# AEMSUCA-R3.net
KiCad netlist of a schematic drawn in EAGLE
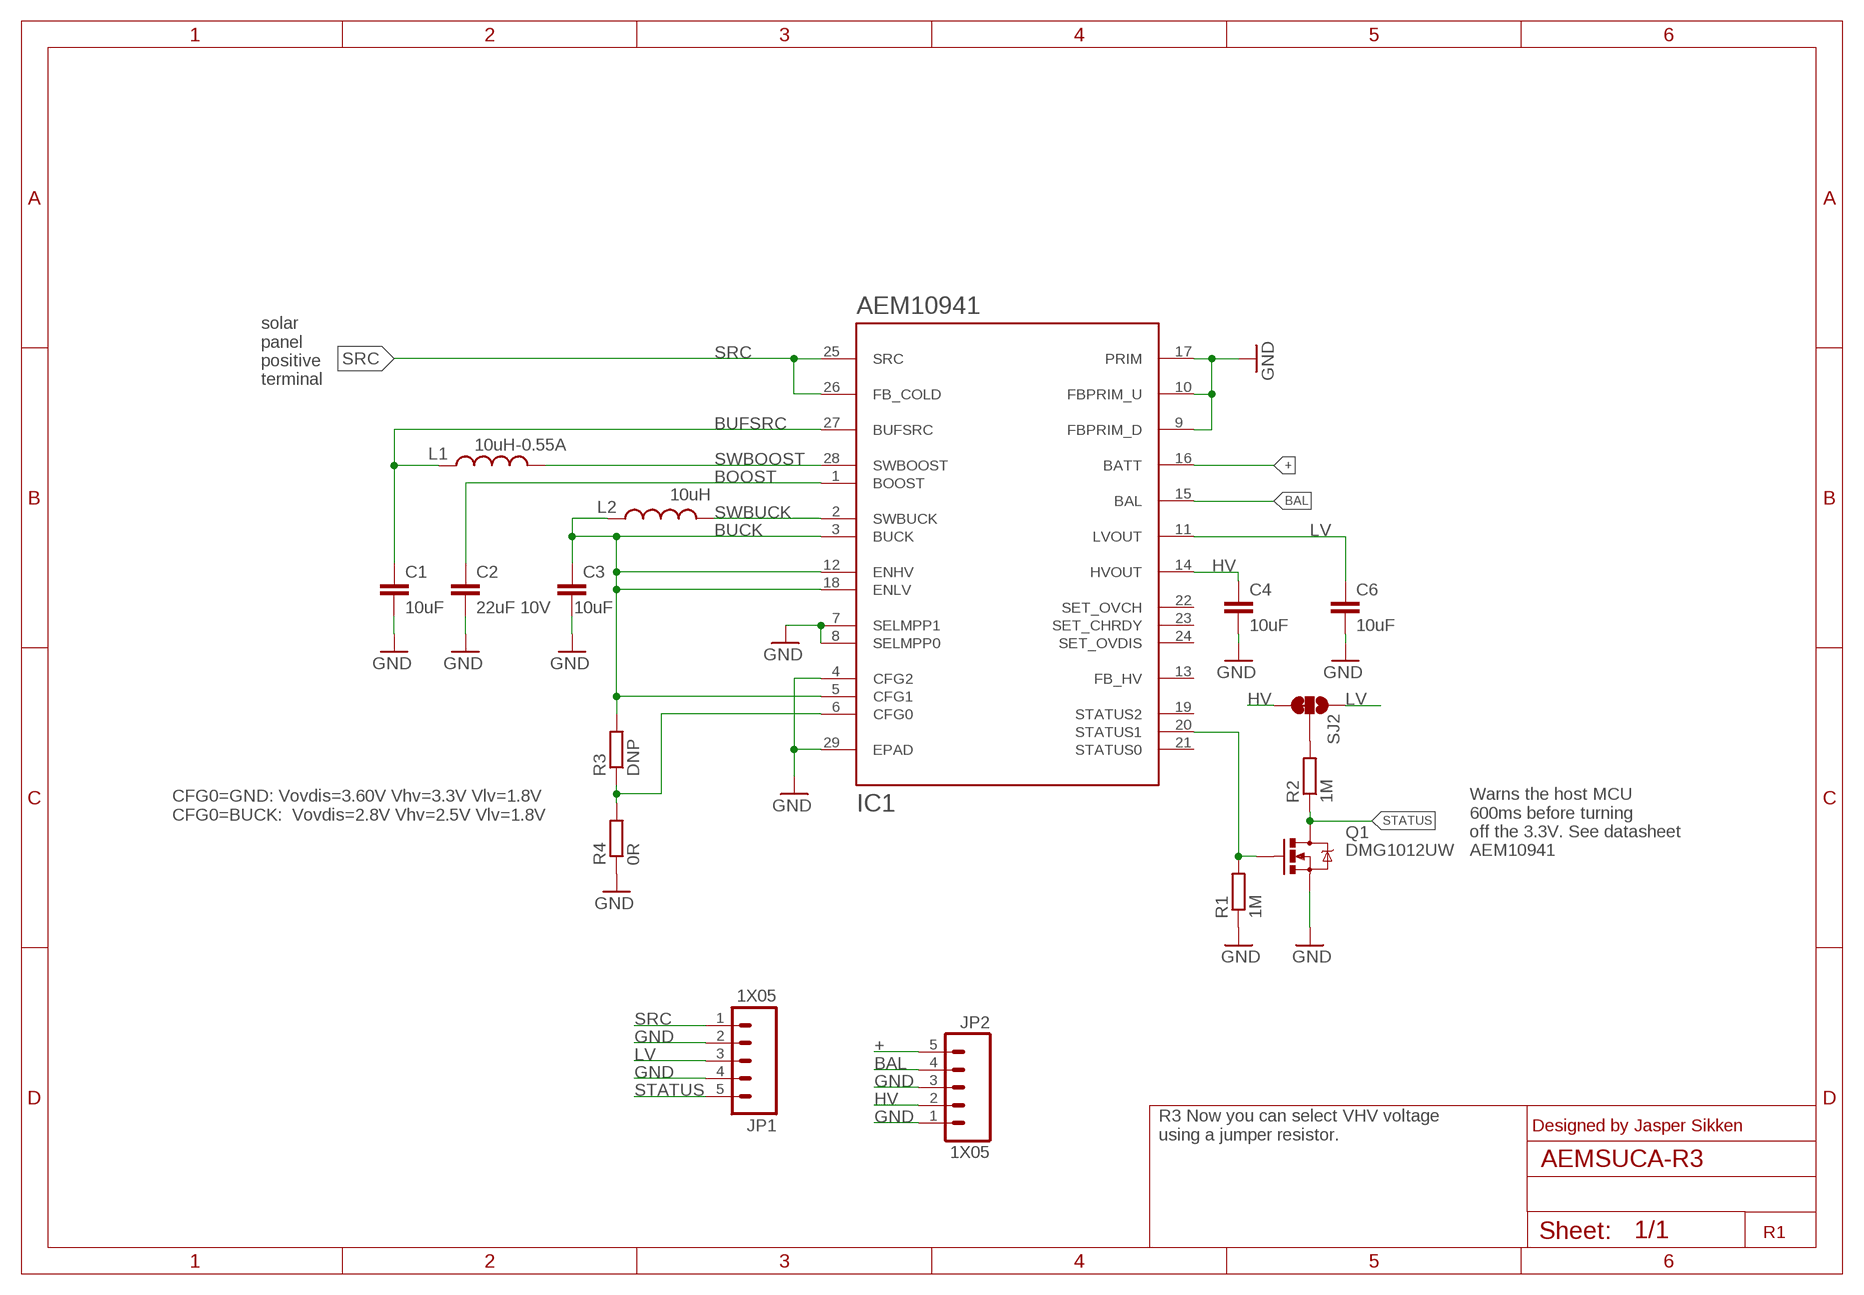
[diagram p0: schematic, sheet 1]

(export (version "E")
  (design (tool "Eeschema 10.0.6"))
  (components
    (comp (ref "C1")
      (value "10uF")
      (footprint "eagle-import:C0603")
      (fields (field (name "MF") "Taiyo Yuden") (field (name "MPN") "LMK107BBJ106MALT"))
      (libsource (lib "eagle-import") (part "C0603_10UF"))
    )
    (comp (ref "C2")
      (value "22uF 10V")
      (footprint "eagle-import:C0603")
      (fields (field (name "MF") "Murata") (field (name "MPN") "GRM188R61A226ME15D"))
      (libsource (lib "eagle-import") (part "C0603_22UF"))
    )
    (comp (ref "C3")
      (value "10uF")
      (footprint "eagle-import:C0603")
      (fields (field (name "MF") "Taiyo Yuden") (field (name "MPN") "LMK107BBJ106MALT"))
      (libsource (lib "eagle-import") (part "C0603_10UF"))
    )
    (comp (ref "C4")
      (value "10uF")
      (footprint "eagle-import:C0603")
      (fields (field (name "MF") "Taiyo Yuden") (field (name "MPN") "LMK107BBJ106MALT"))
      (libsource (lib "eagle-import") (part "C0603_10UF"))
    )
    (comp (ref "C6")
      (value "10uF")
      (footprint "eagle-import:C0603")
      (fields (field (name "MF") "Taiyo Yuden") (field (name "MPN") "LMK107BBJ106MALT"))
      (libsource (lib "eagle-import") (part "C0603_10UF"))
    )
    (comp (ref "IC1")
      (value "AEM10941")
      (footprint "eagle-import:QFN50P505X505X90-28")
      (fields (field (name "MF") "e-peas"))
      (libsource (lib "eagle-import") (part "AEM10941"))
    )
    (comp (ref "JP1")
      (value "1X05")
      (footprint "eagle-import:1X05_2.54MM_ROUND_NOSILK")
      (libsource (lib "eagle-import") (part "1X05"))
    )
    (comp (ref "JP2")
      (value "1X05")
      (footprint "eagle-import:1X05_2.54MM_ROUND_NOSILK")
      (libsource (lib "eagle-import") (part "1X05"))
    )
    (comp (ref "L1")
      (value "10uH-0.55A")
      (footprint "eagle-import:LPS4012")
      (fields (field (name "MF") "Coilcraft") (field (name "MPN") "LPS4012-103MRB"))
      (libsource (lib "eagle-import") (part "L3.9X3.9_10UH_0.55A"))
    )
    (comp (ref "L2")
      (value "10uH")
      (footprint "eagle-import:L0603")
      (fields (field (name "MF") "TDK") (field (name "MPN") "MLZ1608M100WT"))
      (libsource (lib "eagle-import") (part "L0603_10UH"))
    )
    (comp (ref "Q1")
      (value "DMG1012UW")
      (footprint "eagle-import:SOT323")
      (fields (field (name "MF") "Diodes") (field (name "MPN") "DMG1012UW-7"))
      (libsource (lib "eagle-import") (part "MOSFET-N-CHANNEL_DMG1012UW"))
    )
    (comp (ref "R1")
      (value "1M")
      (footprint "eagle-import:R0402")
      (fields (field (name "MF") "Walsin") (field (name "MPN") "WR04X1004FTL"))
      (libsource (lib "eagle-import") (part "R0402_1M"))
    )
    (comp (ref "R2")
      (value "1M")
      (footprint "eagle-import:R0402")
      (fields (field (name "MF") "Walsin") (field (name "MPN") "WR04X1004FTL"))
      (libsource (lib "eagle-import") (part "R0402_1M"))
    )
    (comp (ref "R3")
      (value "DNP")
      (footprint "eagle-import:R0402")
      (fields (field (name "MF") "Walsin") (field (name "MPN") "WR04X1004FTL"))
      (libsource (lib "eagle-import") (part "R0402_1M"))
    )
    (comp (ref "R4")
      (value "0R")
      (footprint "eagle-import:R0402")
      (fields (field (name "MF") "Walsin") (field (name "MPN") "WR04X1004FTL"))
      (libsource (lib "eagle-import") (part "R0402_1M"))
    )
    (comp (ref "SJ2")
      (value "SOLDERJUMPER_3WAY_12SHORT3WAY")
      (footprint "eagle-import:SJ_3S_NC_0402")
      (libsource (lib "eagle-import") (part "SOLDERJUMPER_3WAY_12SHORT3WAY"))
    )
  )
  (nets
    (net (code "1") (name "+") (class "Default")
      (node (ref "IC1") (pin "16") (pinfunction "BATT_16") (pintype "bidirectional"))
      (node (ref "JP2") (pin "5") (pinfunction "5_5") (pintype "passive"))
    )
    (net (code "2") (name "/BOOST") (class "Default")
      (node (ref "C2") (pin "1") (pinfunction "1_1") (pintype "passive"))
      (node (ref "IC1") (pin "1") (pinfunction "BOOST_1") (pintype "bidirectional"))
    )
    (net (code "3") (name "/BUCK") (class "Default")
      (node (ref "C3") (pin "1") (pinfunction "1_1") (pintype "passive"))
      (node (ref "IC1") (pin "12") (pinfunction "ENHV_12") (pintype "bidirectional"))
      (node (ref "IC1") (pin "18") (pinfunction "ENLV_18") (pintype "bidirectional"))
      (node (ref "IC1") (pin "3") (pinfunction "BUCK_3") (pintype "bidirectional"))
      (node (ref "IC1") (pin "5") (pinfunction "CFG1_5") (pintype "bidirectional"))
      (node (ref "L2") (pin "1") (pinfunction "1_1") (pintype "passive"))
      (node (ref "R3") (pin "2") (pinfunction "2_2") (pintype "passive"))
    )
    (net (code "4") (name "/BUFSRC") (class "Default")
      (node (ref "C1") (pin "1") (pinfunction "1_1") (pintype "passive"))
      (node (ref "IC1") (pin "27") (pinfunction "BUFSRC_27") (pintype "power_in"))
      (node (ref "L1") (pin "1") (pinfunction "1_1") (pintype "passive"))
    )
    (net (code "5") (name "/HV") (class "Default")
      (node (ref "C4") (pin "1") (pinfunction "1_1") (pintype "passive"))
      (node (ref "IC1") (pin "14") (pinfunction "HVOUT_14") (pintype "bidirectional"))
      (node (ref "JP2") (pin "2") (pinfunction "2_2") (pintype "passive"))
      (node (ref "SJ2") (pin "1") (pinfunction "1_1") (pintype "passive"))
    )
    (net (code "6") (name "/LV") (class "Default")
      (node (ref "C6") (pin "1") (pinfunction "1_1") (pintype "passive"))
      (node (ref "IC1") (pin "11") (pinfunction "LVOUT_11") (pintype "bidirectional"))
      (node (ref "JP1") (pin "3") (pinfunction "3_3") (pintype "passive"))
      (node (ref "SJ2") (pin "3") (pinfunction "3_3") (pintype "passive"))
    )
    (net (code "7") (name "/SWBOOST") (class "Default")
      (node (ref "IC1") (pin "28") (pinfunction "SWBOOST_28") (pintype "power_in"))
      (node (ref "L1") (pin "2") (pinfunction "2_2") (pintype "passive"))
    )
    (net (code "8") (name "/SWBUCK") (class "Default")
      (node (ref "IC1") (pin "2") (pinfunction "SWBUCK_2") (pintype "bidirectional"))
      (node (ref "L2") (pin "2") (pinfunction "2_2") (pintype "passive"))
    )
    (net (code "9") (name "BAL") (class "Default")
      (node (ref "IC1") (pin "15") (pinfunction "BAL_15") (pintype "bidirectional"))
      (node (ref "JP2") (pin "4") (pinfunction "4_4") (pintype "passive"))
    )
    (net (code "10") (name "GND") (class "Default")
      (node (ref "C1") (pin "2") (pinfunction "2_2") (pintype "passive"))
      (node (ref "C2") (pin "2") (pinfunction "2_2") (pintype "passive"))
      (node (ref "C3") (pin "2") (pinfunction "2_2") (pintype "passive"))
      (node (ref "C4") (pin "2") (pinfunction "2_2") (pintype "passive"))
      (node (ref "C6") (pin "2") (pinfunction "2_2") (pintype "passive"))
      (node (ref "IC1") (pin "10") (pinfunction "FBPRIM_U_10") (pintype "bidirectional"))
      (node (ref "IC1") (pin "17") (pinfunction "PRIM_17") (pintype "bidirectional"))
      (node (ref "IC1") (pin "29") (pinfunction "EPAD_29") (pintype "power_in"))
      (node (ref "IC1") (pin "4") (pinfunction "CFG2_4") (pintype "bidirectional"))
      (node (ref "IC1") (pin "7") (pinfunction "SELMPP1_7") (pintype "bidirectional"))
      (node (ref "IC1") (pin "8") (pinfunction "SELMPP0_8") (pintype "bidirectional"))
      (node (ref "IC1") (pin "9") (pinfunction "FBPRIM_D_9") (pintype "bidirectional"))
      (node (ref "JP1") (pin "2") (pinfunction "2_2") (pintype "passive"))
      (node (ref "JP1") (pin "4") (pinfunction "4_4") (pintype "passive"))
      (node (ref "JP2") (pin "1") (pinfunction "1_1") (pintype "passive"))
      (node (ref "JP2") (pin "3") (pinfunction "3_3") (pintype "passive"))
      (node (ref "Q1") (pin "2") (pinfunction "S_2") (pintype "passive"))
      (node (ref "R1") (pin "1") (pinfunction "1_1") (pintype "passive"))
      (node (ref "R4") (pin "1") (pinfunction "1_1") (pintype "passive"))
    )
    (net (code "11") (name "Net-(IC1-CFG0)") (class "Default")
      (node (ref "IC1") (pin "6") (pinfunction "CFG0_6") (pintype "bidirectional"))
      (node (ref "R3") (pin "1") (pinfunction "1_1") (pintype "passive"))
      (node (ref "R4") (pin "2") (pinfunction "2_2") (pintype "passive"))
    )
    (net (code "12") (name "Net-(IC1-STATUS1)") (class "Default")
      (node (ref "IC1") (pin "20") (pinfunction "STATUS1_20") (pintype "bidirectional"))
      (node (ref "Q1") (pin "1") (pinfunction "G_1") (pintype "passive"))
      (node (ref "R1") (pin "2") (pinfunction "2_2") (pintype "passive"))
    )
    (net (code "13") (name "Net-(R2-Pad2)") (class "Default")
      (node (ref "R2") (pin "2") (pinfunction "2_2") (pintype "passive"))
      (node (ref "SJ2") (pin "2") (pinfunction "2_2") (pintype "passive"))
    )
    (net (code "14") (name "SRC") (class "Default")
      (node (ref "IC1") (pin "25") (pinfunction "SRC_25") (pintype "power_in"))
      (node (ref "IC1") (pin "26") (pinfunction "FB_COLD_26") (pintype "input"))
      (node (ref "JP1") (pin "1") (pinfunction "1_1") (pintype "passive"))
    )
    (net (code "15") (name "STATUS") (class "Default")
      (node (ref "JP1") (pin "5") (pinfunction "5_5") (pintype "passive"))
      (node (ref "Q1") (pin "3") (pinfunction "D_3") (pintype "passive"))
      (node (ref "R2") (pin "1") (pinfunction "1_1") (pintype "passive"))
    )
    (net (code "16") (name "unconnected-(IC1-FB_HV-Pad13)") (class "Default")
      (node (ref "IC1") (pin "13") (pinfunction "FB_HV_13") (pintype "bidirectional"))
    )
    (net (code "17") (name "unconnected-(IC1-SET_CHRDY-Pad23)") (class "Default")
      (node (ref "IC1") (pin "23") (pinfunction "SET_CHRDY_23") (pintype "bidirectional"))
    )
    (net (code "18") (name "unconnected-(IC1-SET_OVCH-Pad22)") (class "Default")
      (node (ref "IC1") (pin "22") (pinfunction "SET_OVCH_22") (pintype "bidirectional"))
    )
    (net (code "19") (name "unconnected-(IC1-SET_OVDIS-Pad24)") (class "Default")
      (node (ref "IC1") (pin "24") (pinfunction "SET_OVDIS_24") (pintype "bidirectional"))
    )
    (net (code "20") (name "unconnected-(IC1-STATUS0-Pad21)") (class "Default")
      (node (ref "IC1") (pin "21") (pinfunction "STATUS0_21") (pintype "bidirectional"))
    )
    (net (code "21") (name "unconnected-(IC1-STATUS2-Pad19)") (class "Default")
      (node (ref "IC1") (pin "19") (pinfunction "STATUS2_19") (pintype "bidirectional"))
    )
  )
)
